# design.net
KiCad netlist of a schematic drawn in EasyEDA Pro
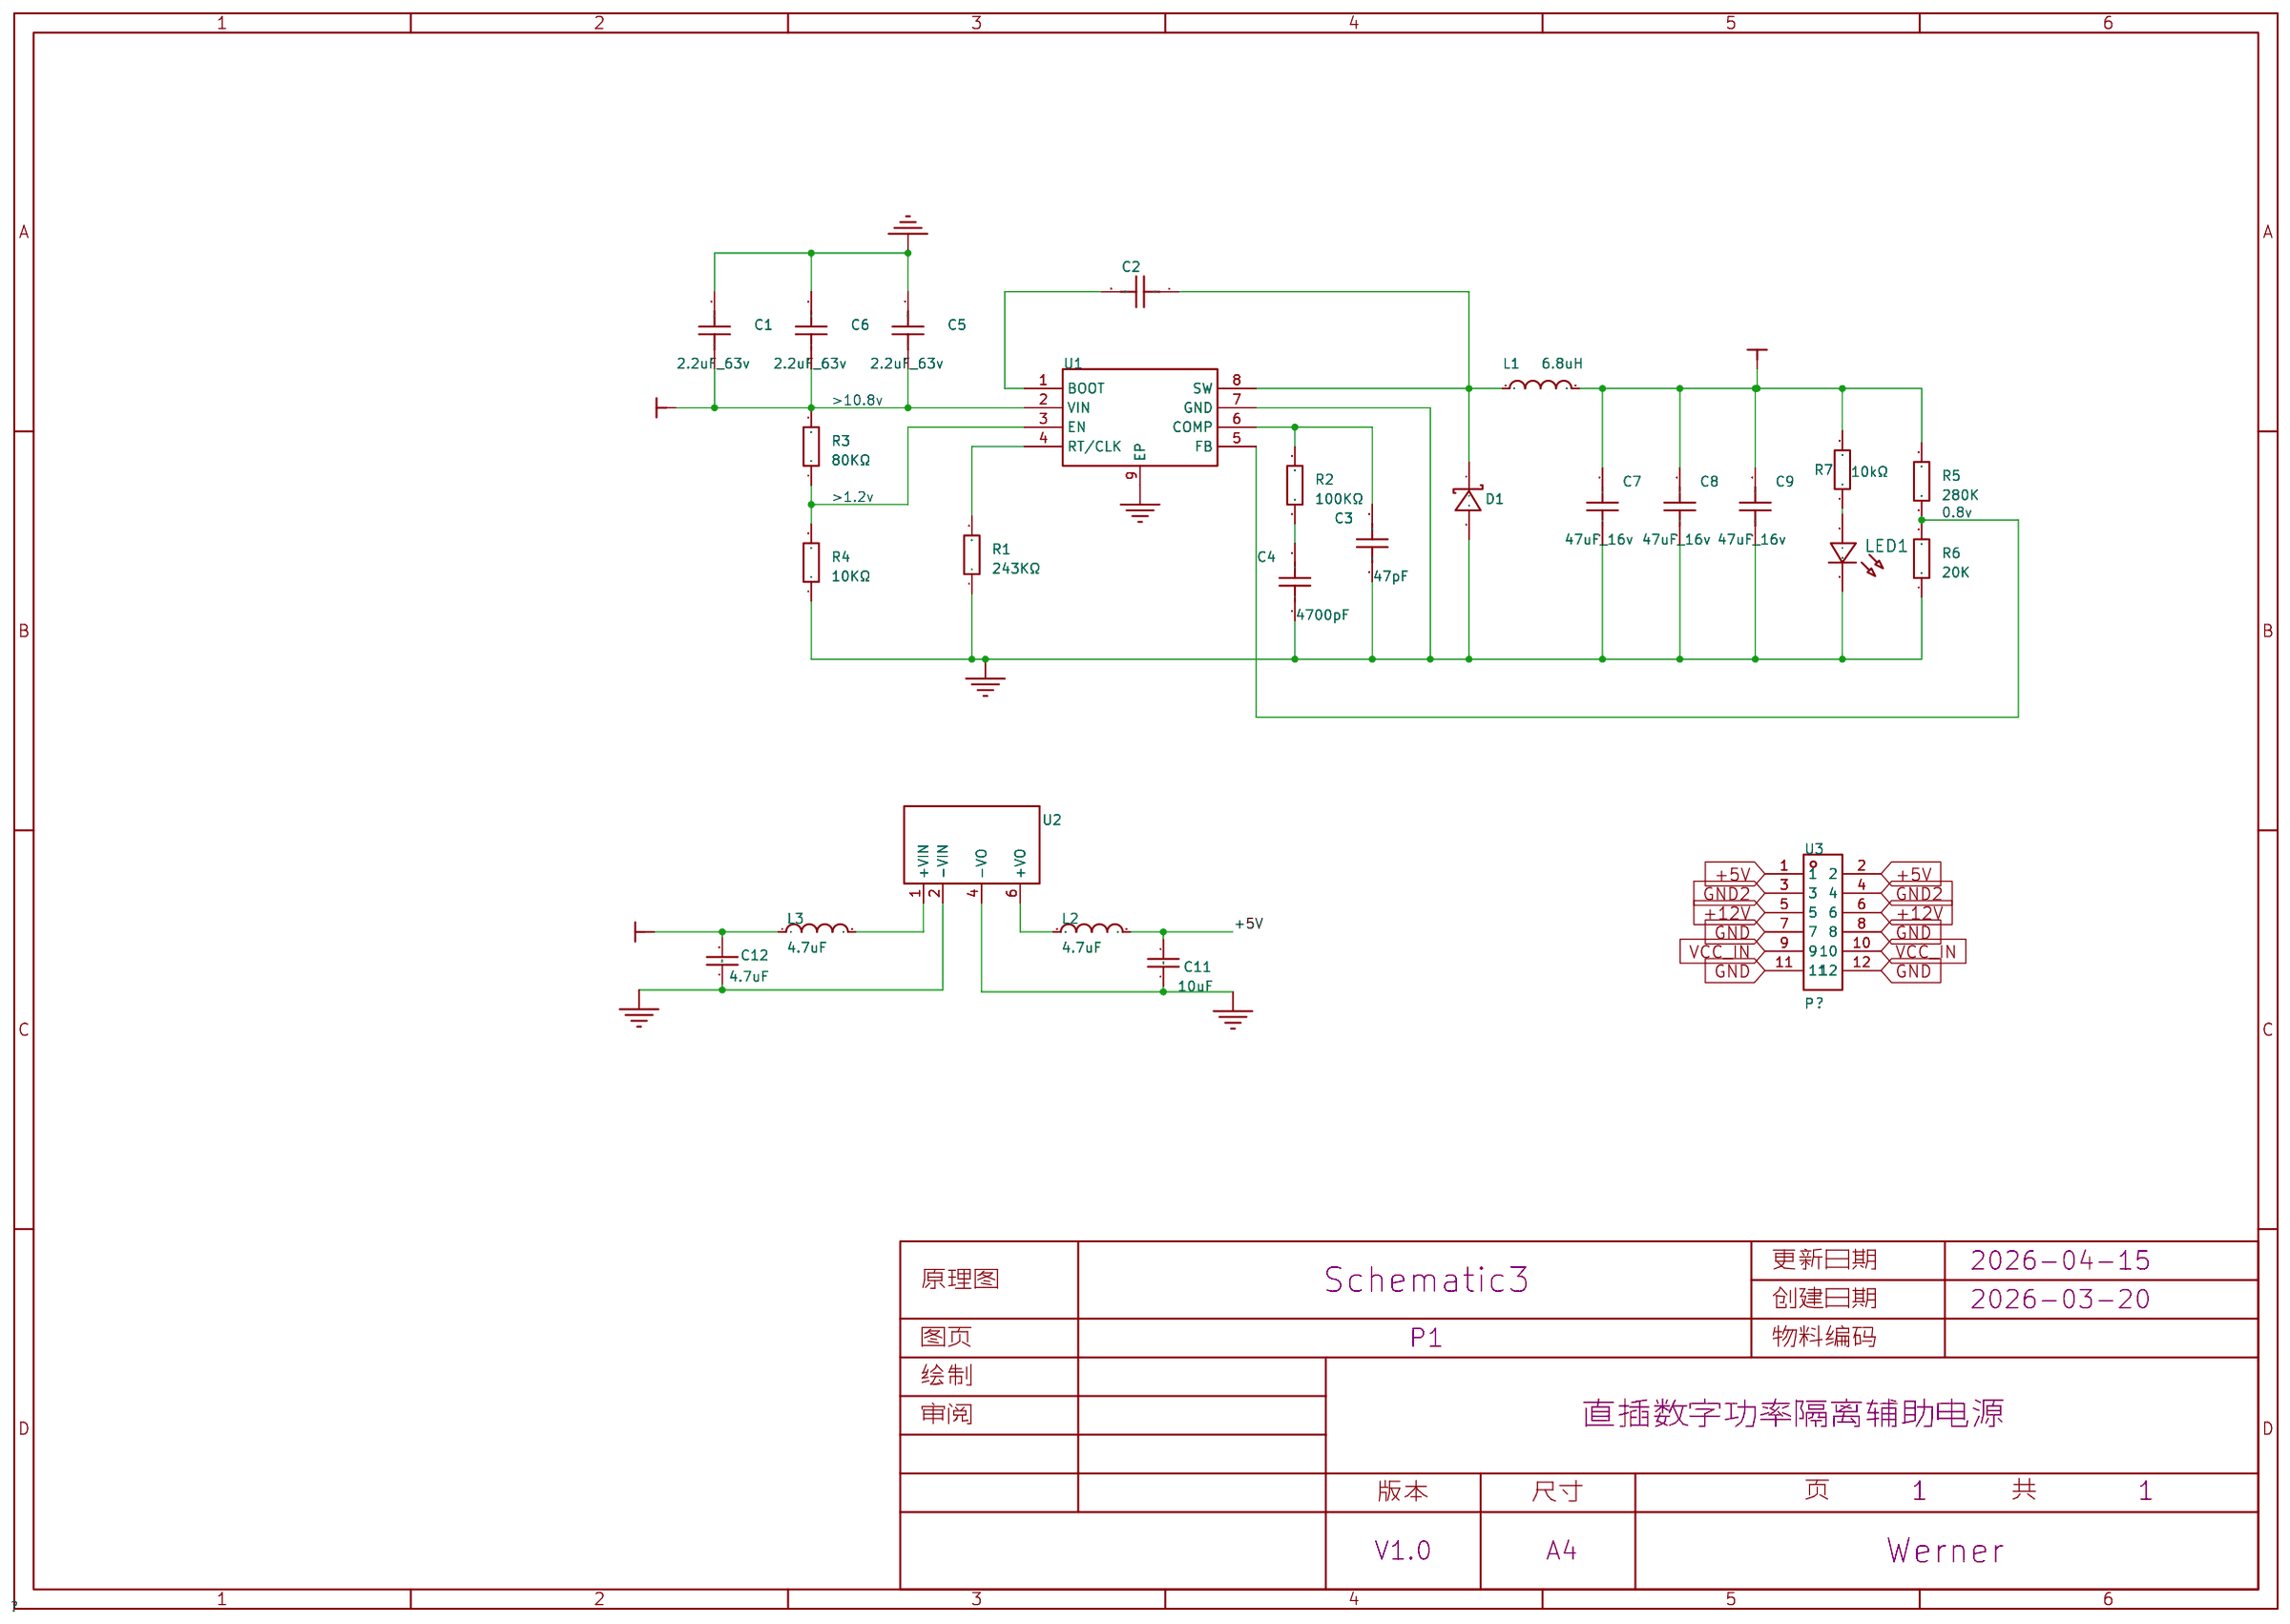
[diagram p0: schematic sheet]

(export (version "E")
  (design (tool "Eeschema 10.0.6"))
  (components
    (comp (ref "C1")
      (value "2.2uF_63v")
      (footprint "easyedapro:C0603")
      (libsource (lib "easyedapro") (part "Capacitance"))
    )
    (comp (ref "C2")
      (value "100nF")
      (footprint "easyedapro:C0603")
      (libsource (lib "easyedapro") (part "Capacitance"))
    )
    (comp (ref "C3")
      (value "47pF")
      (footprint "easyedapro:C0603")
      (libsource (lib "easyedapro") (part "Capacitance"))
    )
    (comp (ref "C4")
      (value "4700pF")
      (footprint "easyedapro:C0603")
      (libsource (lib "easyedapro") (part "Capacitance"))
    )
    (comp (ref "C5")
      (value "2.2uF_63v")
      (footprint "easyedapro:C0603")
      (libsource (lib "easyedapro") (part "Capacitance"))
    )
    (comp (ref "C6")
      (value "2.2uF_63v")
      (footprint "easyedapro:C0603")
      (libsource (lib "easyedapro") (part "Capacitance"))
    )
    (comp (ref "C7")
      (value "47uF_16v")
      (footprint "easyedapro:C0603")
      (libsource (lib "easyedapro") (part "Capacitance"))
    )
    (comp (ref "C8")
      (value "47uF_16v")
      (footprint "easyedapro:C0603")
      (libsource (lib "easyedapro") (part "Capacitance"))
    )
    (comp (ref "C9")
      (value "47uF_16v")
      (footprint "easyedapro:C0603")
      (libsource (lib "easyedapro") (part "Capacitance"))
    )
    (comp (ref "C11")
      (value "10uF")
      (footprint "easyedapro:C0603")
      (libsource (lib "easyedapro") (part "C0603"))
    )
    (comp (ref "C12")
      (value "4.7uF")
      (footprint "easyedapro:C0603")
      (libsource (lib "easyedapro") (part "C0603"))
    )
    (comp (ref "D1")
      (value "SS3200")
      (footprint "easyedapro:SMA_L4.3-W2.6-LS5.2-RD")
      (description "正向压降(Vf):950mV@3A;直流反向耐压(Vr):200V;平均整流电流(Io):3A;")
      (fields (field (name "Manufacturer") "MDD"))
      (libsource (lib "easyedapro") (part "SS3200_C65001"))
    )
    (comp (ref "L1")
      (value "6.8uH")
      (footprint "easyedapro:IND-SMD_L7.1-W6.6")
      (description "电感值:10uH;精度:±20%;饱和电流(Isat):4.5A;类型:一体成型电感;")
      (fields (field (name "Manufacturer Part") "D0630HP-100MT") (field (name "Manufacturer") "DEYAN(德砚电子)"))
      (libsource (lib "easyedapro") (part "D0630HP-100MT"))
    )
    (comp (ref "L2")
      (value "4.7uF")
      (footprint "easyedapro:IND-SMD_L4.9-W4.4_MAPM0420F")
      (description "电感值:10uH;精度:±20%;额定电流:1.5A;饱和电流(Isat):1.8A;")
      (fields (field (name "Manufacturer Part") "HA42-100MTP01") (field (name "Manufacturer") "FH(风华)"))
      (libsource (lib "easyedapro") (part "HA42-100MTP01"))
    )
    (comp (ref "L3")
      (value "4.7uF")
      (footprint "easyedapro:IND-SMD_L4.9-W4.4_MAPM0420F")
      (description "电感值:10uH;精度:±20%;额定电流:1.5A;饱和电流(Isat):1.8A;")
      (fields (field (name "Manufacturer Part") "HA42-100MTP01") (field (name "Manufacturer") "FH(风华)"))
      (libsource (lib "easyedapro") (part "HA42-100MTP01"))
    )
    (comp (ref "LED1")
      (value "~")
      (footprint "easyedapro:LED_0603")
      (libsource (lib "easyedapro") (part "LED_R"))
    )
    (comp (ref "R1")
      (value "243KΩ")
      (footprint "easyedapro:R0603")
      (libsource (lib "easyedapro") (part "电阻_1"))
    )
    (comp (ref "R2")
      (value "100KΩ")
      (footprint "easyedapro:R0603")
      (libsource (lib "easyedapro") (part "电阻_1"))
    )
    (comp (ref "R3")
      (value "80KΩ")
      (footprint "easyedapro:R0603")
      (libsource (lib "easyedapro") (part "电阻_1"))
    )
    (comp (ref "R4")
      (value "10KΩ")
      (footprint "easyedapro:R0603")
      (libsource (lib "easyedapro") (part "电阻_1"))
    )
    (comp (ref "R5")
      (value "280K")
      (footprint "easyedapro:R0603")
      (libsource (lib "easyedapro") (part "电阻_1"))
    )
    (comp (ref "R6")
      (value "20K")
      (footprint "easyedapro:R0603")
      (libsource (lib "easyedapro") (part "电阻_1"))
    )
    (comp (ref "R7")
      (value "10kΩ")
      (footprint "easyedapro:R0805")
      (description "电阻类型:厚膜电阻;阻值:5.1kΩ;精度:±1%;功率:125mW;最大工作电压:150V;温度系数:±100ppm/℃;")
      (fields
        (field (name "Manufacturer Part") "0805W8F5101T5E")
        (field (name "Manufacturer") "UNI-ROYAL(厚声)")
      )
      (libsource (lib "easyedapro") (part "0805W8F5101T5E"))
    )
    (comp (ref "U1")
      (value "TPS54560DDAR")
      (footprint "easyedapro:SOIC-8_L5.0-W4.0-P1.27-LS6.0-BL-EP2.0")
      (description "功能类型:降压型;输出类型:可调;工作电压:4.5V~60V;输出电压:800mV~58.8V;输出电流:5A;")
      (fields (field (name "Manufacturer") "TI(德州仪器)"))
      (libsource (lib "easyedapro") (part "TPS54560DDAR"))
    )
    (comp (ref "U2")
      (value "B1205S-2WR3")
      (footprint "easyedapro:PWRM-TH_4P-L19.7-W7.1_B1205S-2WR3")
      (fields (field (name "Manufacturer") "YLPTEC(易川)"))
      (libsource (lib "easyedapro") (part "B1205S-2WR3_C2992387"))
    )
    (comp (ref "U3") (value "P？") (libsource (lib "easyedapro") (part "辅助电源双层贴片排针6X2P")))
  )
  (nets
    (net (code "1") (name "+5V") (class "Default")
      (node (ref "C11") (pin "2") (pinfunction "2_2") (pintype "input"))
      (node (ref "L2") (pin "2") (pinfunction "2_2") (pintype "unspecified"))
      (node (ref "U3") (pin "1") (pinfunction "1_1") (pintype "unspecified"))
      (node (ref "U3") (pin "2") (pinfunction "2_2") (pintype "unspecified"))
    )
    (net (code "2") (name "+12V") (class "Default")
      (node (ref "C12") (pin "2") (pinfunction "2_2") (pintype "input"))
      (node (ref "C7") (pin "2") (pinfunction "2_2") (pintype "input"))
      (node (ref "C8") (pin "2") (pinfunction "2_2") (pintype "input"))
      (node (ref "C9") (pin "2") (pinfunction "2_2") (pintype "input"))
      (node (ref "L1") (pin "2") (pinfunction "2_2") (pintype "unspecified"))
      (node (ref "L3") (pin "1") (pinfunction "1_1") (pintype "unspecified"))
      (node (ref "R5") (pin "2") (pinfunction "2_2") (pintype "input"))
      (node (ref "R7") (pin "2") (pinfunction "2_2") (pintype "input"))
      (node (ref "U3") (pin "5") (pinfunction "5_5") (pintype "unspecified"))
      (node (ref "U3") (pin "6") (pinfunction "6_6") (pintype "unspecified"))
    )
    (net (code "3") (name "GND") (class "Default")
      (node (ref "C1") (pin "2") (pinfunction "2_2") (pintype "input"))
      (node (ref "C12") (pin "1") (pinfunction "1_1") (pintype "input"))
      (node (ref "C3") (pin "1") (pinfunction "1_1") (pintype "input"))
      (node (ref "C4") (pin "1") (pinfunction "1_1") (pintype "input"))
      (node (ref "C5") (pin "2") (pinfunction "2_2") (pintype "input"))
      (node (ref "C6") (pin "2") (pinfunction "2_2") (pintype "input"))
      (node (ref "C7") (pin "1") (pinfunction "1_1") (pintype "input"))
      (node (ref "C8") (pin "1") (pinfunction "1_1") (pintype "input"))
      (node (ref "C9") (pin "1") (pinfunction "1_1") (pintype "input"))
      (node (ref "D1") (pin "2") (pinfunction "A_2") (pintype "unspecified"))
      (node (ref "LED1") (pin "1") (pinfunction "C_1") (pintype "input"))
      (node (ref "R1") (pin "1") (pinfunction "1_1") (pintype "input"))
      (node (ref "R4") (pin "1") (pinfunction "1_1") (pintype "input"))
      (node (ref "R6") (pin "1") (pinfunction "1_1") (pintype "input"))
      (node (ref "U1") (pin "7") (pinfunction "GND_7") (pintype "unspecified"))
      (node (ref "U1") (pin "9") (pinfunction "EP_9") (pintype "unspecified"))
      (node (ref "U2") (pin "2") (pinfunction "-VIN_2") (pintype "unspecified"))
      (node (ref "U3") (pin "11") (pinfunction "11_11") (pintype "unspecified"))
      (node (ref "U3") (pin "12") (pinfunction "12_12") (pintype "unspecified"))
      (node (ref "U3") (pin "7") (pinfunction "7_7") (pintype "unspecified"))
      (node (ref "U3") (pin "8") (pinfunction "8_8") (pintype "unspecified"))
    )
    (net (code "4") (name "GND2") (class "Default")
      (node (ref "C11") (pin "1") (pinfunction "1_1") (pintype "input"))
      (node (ref "U2") (pin "4") (pinfunction "-VO_4") (pintype "unspecified"))
      (node (ref "U3") (pin "3") (pinfunction "3_3") (pintype "unspecified"))
      (node (ref "U3") (pin "4") (pinfunction "4_4") (pintype "unspecified"))
    )
    (net (code "5") (name "Net-(C4-Pad2)") (class "Default")
      (node (ref "C4") (pin "2") (pinfunction "2_2") (pintype "input"))
      (node (ref "R2") (pin "1") (pinfunction "1_1") (pintype "input"))
    )
    (net (code "6") (name "Net-(D1-K)") (class "Default")
      (node (ref "C2") (pin "1") (pinfunction "1_1") (pintype "input"))
      (node (ref "D1") (pin "1") (pinfunction "K_1") (pintype "unspecified"))
      (node (ref "L1") (pin "1") (pinfunction "1_1") (pintype "unspecified"))
      (node (ref "U1") (pin "8") (pinfunction "SW_8") (pintype "unspecified"))
    )
    (net (code "7") (name "Net-(LED1-A)") (class "Default")
      (node (ref "LED1") (pin "2") (pinfunction "A_2") (pintype "input"))
      (node (ref "R7") (pin "1") (pinfunction "1_1") (pintype "input"))
    )
    (net (code "8") (name "Net-(U1-BOOT)") (class "Default")
      (node (ref "C2") (pin "2") (pinfunction "2_2") (pintype "input"))
      (node (ref "U1") (pin "1") (pinfunction "BOOT_1") (pintype "unspecified"))
    )
    (net (code "9") (name "Net-(U1-COMP)") (class "Default")
      (node (ref "C3") (pin "2") (pinfunction "2_2") (pintype "input"))
      (node (ref "R2") (pin "2") (pinfunction "2_2") (pintype "input"))
      (node (ref "U1") (pin "6") (pinfunction "COMP_6") (pintype "unspecified"))
    )
    (net (code "10") (name "Net-(U1-EN)") (class "Default")
      (node (ref "R3") (pin "1") (pinfunction "1_1") (pintype "input"))
      (node (ref "R4") (pin "2") (pinfunction "2_2") (pintype "input"))
      (node (ref "U1") (pin "3") (pinfunction "EN_3") (pintype "unspecified"))
    )
    (net (code "11") (name "Net-(U1-FB)") (class "Default")
      (node (ref "R5") (pin "1") (pinfunction "1_1") (pintype "input"))
      (node (ref "R6") (pin "2") (pinfunction "2_2") (pintype "input"))
      (node (ref "U1") (pin "5") (pinfunction "FB_5") (pintype "unspecified"))
    )
    (net (code "12") (name "Net-(U1-RT{slash}CLK)") (class "Default")
      (node (ref "R1") (pin "2") (pinfunction "2_2") (pintype "input"))
      (node (ref "U1") (pin "4") (pinfunction "RT/CLK_4") (pintype "unspecified"))
    )
    (net (code "13") (name "Net-(U2-+VIN)") (class "Default")
      (node (ref "L3") (pin "2") (pinfunction "2_2") (pintype "unspecified"))
      (node (ref "U2") (pin "1") (pinfunction "+VIN_1") (pintype "unspecified"))
    )
    (net (code "14") (name "Net-(U2-+VO)") (class "Default")
      (node (ref "L2") (pin "1") (pinfunction "1_1") (pintype "unspecified"))
      (node (ref "U2") (pin "6") (pinfunction "+VO_6") (pintype "unspecified"))
    )
    (net (code "15") (name "VCC_IN") (class "Default")
      (node (ref "C1") (pin "1") (pinfunction "1_1") (pintype "input"))
      (node (ref "C5") (pin "1") (pinfunction "1_1") (pintype "input"))
      (node (ref "C6") (pin "1") (pinfunction "1_1") (pintype "input"))
      (node (ref "R3") (pin "2") (pinfunction "2_2") (pintype "input"))
      (node (ref "U1") (pin "2") (pinfunction "VIN_2") (pintype "unspecified"))
      (node (ref "U3") (pin "10") (pinfunction "10_10") (pintype "unspecified"))
      (node (ref "U3") (pin "9") (pinfunction "9_9") (pintype "unspecified"))
    )
  )
)
